# radio_interface.net
KiCad netlist of a schematic drawn in EAGLE
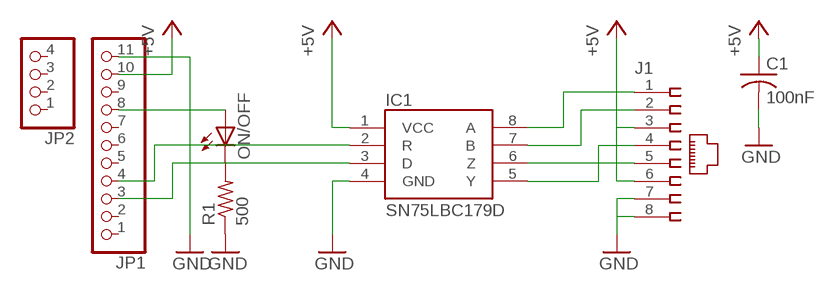
[diagram p0: schematic, sheet 1]

(export (version "E")
  (design (tool "Eeschema 10.0.6"))
  (components
    (comp (ref "C1")
      (value "100nF")
      (footprint "eagle-import:C0805")
      (libsource (lib "eagle-import") (part "C-USC0805"))
    )
    (comp (ref "IC1")
      (value "SN75LBC179D")
      (footprint "eagle-import:SO08")
      (libsource (lib "eagle-import") (part "SN75LBC179D"))
    )
    (comp (ref "J1")
      (value "215877-7")
      (footprint "eagle-import:215877-7")
      (libsource (lib "eagle-import") (part "215877-7"))
    )
    (comp (ref "JP1")
      (value "PINHD-1X11")
      (footprint "eagle-import:1X11")
      (libsource (lib "eagle-import") (part "PINHD-1X11"))
    )
    (comp (ref "JP2")
      (value "PINHD-1X4")
      (footprint "eagle-import:1X04")
      (libsource (lib "eagle-import") (part "PINHD-1X4"))
    )
    (comp (ref "ON/OFF")
      (value "LED5MM")
      (footprint "eagle-import:LED5MM")
      (libsource (lib "eagle-import") (part "LED5MM"))
    )
    (comp (ref "R1")
      (value "500")
      (footprint "eagle-import:R0805")
      (libsource (lib "eagle-import") (part "R-US_R0805"))
    )
  )
  (nets
    (net (code "1") (name "+5V") (class "Default")
      (node (ref "C1") (pin "1") (pinfunction "1_1") (pintype "passive"))
      (node (ref "IC1") (pin "1") (pinfunction "VCC_1") (pintype "power_in"))
      (node (ref "J1") (pin "3") (pinfunction "3_3") (pintype "passive"))
      (node (ref "J1") (pin "6") (pinfunction "6_6") (pintype "passive"))
      (node (ref "JP1") (pin "10") (pinfunction "10_10") (pintype "passive"))
    )
    (net (code "2") (name "GND") (class "Default")
      (node (ref "C1") (pin "2") (pinfunction "2_2") (pintype "passive"))
      (node (ref "IC1") (pin "4") (pinfunction "GND_4") (pintype "power_in"))
      (node (ref "J1") (pin "7") (pinfunction "7_7") (pintype "passive"))
      (node (ref "J1") (pin "8") (pinfunction "8_8") (pintype "passive"))
      (node (ref "JP1") (pin "11") (pinfunction "11_11") (pintype "passive"))
      (node (ref "R1") (pin "1") (pinfunction "1_1") (pintype "passive"))
    )
    (net (code "3") (name "Net-(IC1-A)") (class "Default")
      (node (ref "IC1") (pin "8") (pinfunction "A_8") (pintype "input"))
      (node (ref "J1") (pin "1") (pinfunction "1_1") (pintype "passive"))
    )
    (net (code "4") (name "Net-(IC1-B)") (class "Default")
      (node (ref "IC1") (pin "7") (pinfunction "B_7") (pintype "input"))
      (node (ref "J1") (pin "2") (pinfunction "2_2") (pintype "passive"))
    )
    (net (code "5") (name "Net-(IC1-D)") (class "Default")
      (node (ref "IC1") (pin "3") (pinfunction "D_3") (pintype "input"))
      (node (ref "JP1") (pin "3") (pinfunction "3_3") (pintype "passive"))
    )
    (net (code "6") (name "Net-(IC1-R)") (class "Default")
      (node (ref "IC1") (pin "2") (pinfunction "R_2") (pintype "output"))
      (node (ref "JP1") (pin "4") (pinfunction "4_4") (pintype "passive"))
    )
    (net (code "7") (name "Net-(IC1-Y)") (class "Default")
      (node (ref "IC1") (pin "5") (pinfunction "Y_5") (pintype "output"))
      (node (ref "J1") (pin "4") (pinfunction "4_4") (pintype "passive"))
    )
    (net (code "8") (name "Net-(IC1-Z)") (class "Default")
      (node (ref "IC1") (pin "6") (pinfunction "Z_6") (pintype "output"))
      (node (ref "J1") (pin "5") (pinfunction "5_5") (pintype "passive"))
    )
    (net (code "9") (name "Net-(JP1-Pad8)") (class "Default")
      (node (ref "JP1") (pin "8") (pinfunction "8_8") (pintype "passive"))
      (node (ref "ON/OFF") (pin "A") (pinfunction "A_A") (pintype "passive"))
    )
    (net (code "10") (name "Net-(ON/OFF-C)") (class "Default")
      (node (ref "ON/OFF") (pin "K") (pinfunction "C_K") (pintype "passive"))
      (node (ref "R1") (pin "2") (pinfunction "2_2") (pintype "passive"))
    )
    (net (code "11") (name "unconnected-(JP1-Pad1)") (class "Default")
      (node (ref "JP1") (pin "1") (pinfunction "1_1") (pintype "passive"))
    )
    (net (code "12") (name "unconnected-(JP1-Pad2)") (class "Default")
      (node (ref "JP1") (pin "2") (pinfunction "2_2") (pintype "passive"))
    )
    (net (code "13") (name "unconnected-(JP1-Pad5)") (class "Default")
      (node (ref "JP1") (pin "5") (pinfunction "5_5") (pintype "passive"))
    )
    (net (code "14") (name "unconnected-(JP1-Pad6)") (class "Default")
      (node (ref "JP1") (pin "6") (pinfunction "6_6") (pintype "passive"))
    )
    (net (code "15") (name "unconnected-(JP1-Pad7)") (class "Default")
      (node (ref "JP1") (pin "7") (pinfunction "7_7") (pintype "passive"))
    )
    (net (code "16") (name "unconnected-(JP1-Pad9)") (class "Default")
      (node (ref "JP1") (pin "9") (pinfunction "9_9") (pintype "passive"))
    )
    (net (code "17") (name "unconnected-(JP2-Pad1)") (class "Default")
      (node (ref "JP2") (pin "1") (pinfunction "1_1") (pintype "passive"))
    )
    (net (code "18") (name "unconnected-(JP2-Pad2)") (class "Default")
      (node (ref "JP2") (pin "2") (pinfunction "2_2") (pintype "passive"))
    )
    (net (code "19") (name "unconnected-(JP2-Pad3)") (class "Default")
      (node (ref "JP2") (pin "3") (pinfunction "3_3") (pintype "passive"))
    )
    (net (code "20") (name "unconnected-(JP2-Pad4)") (class "Default")
      (node (ref "JP2") (pin "4") (pinfunction "4_4") (pintype "passive"))
    )
  )
)
